# esp32c2_devboard.net
KiCad netlist of a schematic drawn in Altium Designer
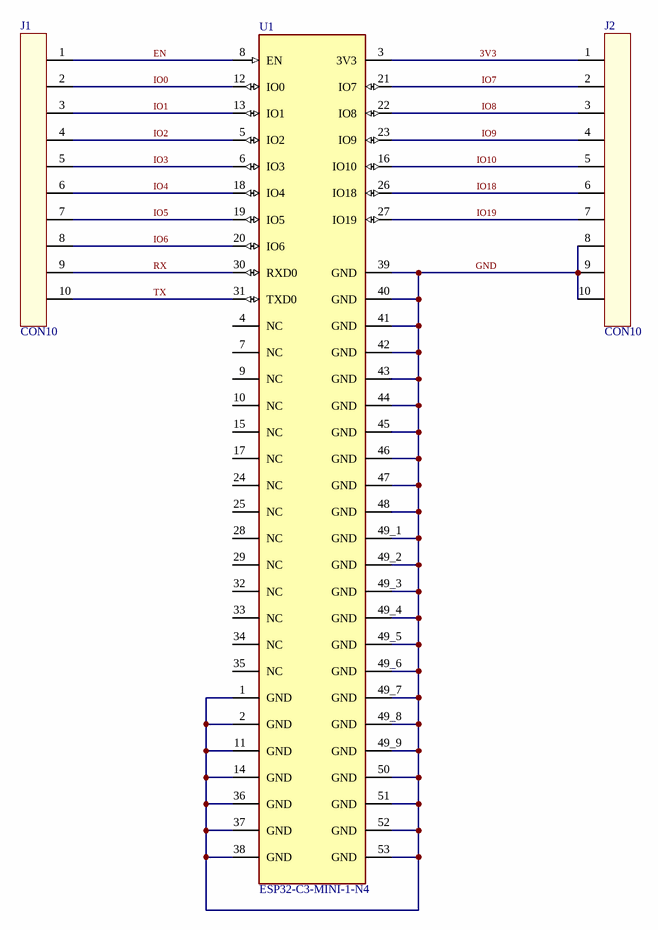
[diagram p0: esp32c2_devboard.SchDoc]

(export (version "E")
  (design (tool "Eeschema 10.0.6"))
  (components
    (comp (ref "J1") (value "CON10") (footprint "CON10") (libsource (lib "") (part "CON10_1")))
    (comp (ref "J2") (value "CON10") (footprint "CON10") (libsource (lib "esp32c2_devboard") (part "CON10")))
    (comp (ref "U1")
      (value "ESP32-C3-MINI-1-N4")
      (footprint "XCVR_ESP32-C3-MINI-1-N4")
      (fields (field (name "MF") "Espressif Systems"))
      (libsource (lib "esp32c2_devboard") (part "ESP32-C3-MINI-1-N4"))
    )
  )
  (nets
    (net (code "1") (name "/3V3") (class "Default")
      (node (ref "J2") (pin "1") (pintype "passive"))
      (node (ref "U1") (pin "3") (pinfunction "3V3_3") (pintype "power_in"))
    )
    (net (code "2") (name "/EN") (class "Default")
      (node (ref "J1") (pin "1") (pintype "passive"))
      (node (ref "U1") (pin "8") (pinfunction "EN_8") (pintype "input"))
    )
    (net (code "3") (name "/GND") (class "Default")
      (node (ref "J2") (pin "10") (pintype "passive"))
      (node (ref "J2") (pin "8") (pintype "passive"))
      (node (ref "J2") (pin "9") (pintype "passive"))
      (node (ref "U1") (pin "1") (pinfunction "GND_1") (pintype "power_in"))
      (node (ref "U1") (pin "11") (pinfunction "GND_11") (pintype "power_in"))
      (node (ref "U1") (pin "14") (pinfunction "GND_14") (pintype "power_in"))
      (node (ref "U1") (pin "2") (pinfunction "GND_2") (pintype "power_in"))
      (node (ref "U1") (pin "36") (pinfunction "GND_36") (pintype "power_in"))
      (node (ref "U1") (pin "37") (pinfunction "GND_37") (pintype "power_in"))
      (node (ref "U1") (pin "38") (pinfunction "GND_38") (pintype "power_in"))
      (node (ref "U1") (pin "39") (pinfunction "GND_39") (pintype "power_in"))
      (node (ref "U1") (pin "40") (pinfunction "GND_40") (pintype "power_in"))
      (node (ref "U1") (pin "41") (pinfunction "GND_41") (pintype "power_in"))
      (node (ref "U1") (pin "42") (pinfunction "GND_42") (pintype "power_in"))
      (node (ref "U1") (pin "43") (pinfunction "GND_43") (pintype "power_in"))
      (node (ref "U1") (pin "44") (pinfunction "GND_44") (pintype "power_in"))
      (node (ref "U1") (pin "45") (pinfunction "GND_45") (pintype "power_in"))
      (node (ref "U1") (pin "46") (pinfunction "GND_46") (pintype "power_in"))
      (node (ref "U1") (pin "47") (pinfunction "GND_47") (pintype "power_in"))
      (node (ref "U1") (pin "48") (pinfunction "GND_48") (pintype "power_in"))
      (node (ref "U1") (pin "49_1") (pinfunction "GND_49_1") (pintype "power_in"))
      (node (ref "U1") (pin "49_2") (pinfunction "GND_49_2") (pintype "power_in"))
      (node (ref "U1") (pin "49_3") (pinfunction "GND_49_3") (pintype "power_in"))
      (node (ref "U1") (pin "49_4") (pinfunction "GND_49_4") (pintype "power_in"))
      (node (ref "U1") (pin "49_5") (pinfunction "GND_49_5") (pintype "power_in"))
      (node (ref "U1") (pin "49_6") (pinfunction "GND_49_6") (pintype "power_in"))
      (node (ref "U1") (pin "49_7") (pinfunction "GND_49_7") (pintype "power_in"))
      (node (ref "U1") (pin "49_8") (pinfunction "GND_49_8") (pintype "power_in"))
      (node (ref "U1") (pin "49_9") (pinfunction "GND_49_9") (pintype "power_in"))
      (node (ref "U1") (pin "50") (pinfunction "GND_50") (pintype "power_in"))
      (node (ref "U1") (pin "51") (pinfunction "GND_51") (pintype "power_in"))
      (node (ref "U1") (pin "52") (pinfunction "GND_52") (pintype "power_in"))
      (node (ref "U1") (pin "53") (pinfunction "GND_53") (pintype "power_in"))
    )
    (net (code "4") (name "/IO0") (class "Default")
      (node (ref "J1") (pin "2") (pintype "passive"))
      (node (ref "U1") (pin "12") (pinfunction "IO0_12") (pintype "bidirectional"))
    )
    (net (code "5") (name "/IO1") (class "Default")
      (node (ref "J1") (pin "3") (pintype "passive"))
      (node (ref "U1") (pin "13") (pinfunction "IO1_13") (pintype "bidirectional"))
    )
    (net (code "6") (name "/IO2") (class "Default")
      (node (ref "J1") (pin "4") (pintype "passive"))
      (node (ref "U1") (pin "5") (pinfunction "IO2_5") (pintype "bidirectional"))
    )
    (net (code "7") (name "/IO3") (class "Default")
      (node (ref "J1") (pin "5") (pintype "passive"))
      (node (ref "U1") (pin "6") (pinfunction "IO3_6") (pintype "bidirectional"))
    )
    (net (code "8") (name "/IO4") (class "Default")
      (node (ref "J1") (pin "6") (pintype "passive"))
      (node (ref "U1") (pin "18") (pinfunction "IO4_18") (pintype "bidirectional"))
    )
    (net (code "9") (name "/IO5") (class "Default")
      (node (ref "J1") (pin "7") (pintype "passive"))
      (node (ref "U1") (pin "19") (pinfunction "IO5_19") (pintype "bidirectional"))
    )
    (net (code "10") (name "/IO6") (class "Default")
      (node (ref "J1") (pin "8") (pintype "passive"))
      (node (ref "U1") (pin "20") (pinfunction "IO6_20") (pintype "bidirectional"))
    )
    (net (code "11") (name "/IO7") (class "Default")
      (node (ref "J2") (pin "2") (pintype "passive"))
      (node (ref "U1") (pin "21") (pinfunction "IO7_21") (pintype "bidirectional"))
    )
    (net (code "12") (name "/IO8") (class "Default")
      (node (ref "J2") (pin "3") (pintype "passive"))
      (node (ref "U1") (pin "22") (pinfunction "IO8_22") (pintype "bidirectional"))
    )
    (net (code "13") (name "/IO9") (class "Default")
      (node (ref "J2") (pin "4") (pintype "passive"))
      (node (ref "U1") (pin "23") (pinfunction "IO9_23") (pintype "bidirectional"))
    )
    (net (code "14") (name "/IO10") (class "Default")
      (node (ref "J2") (pin "5") (pintype "passive"))
      (node (ref "U1") (pin "16") (pinfunction "IO10_16") (pintype "bidirectional"))
    )
    (net (code "15") (name "/IO18") (class "Default")
      (node (ref "J2") (pin "6") (pintype "passive"))
      (node (ref "U1") (pin "26") (pinfunction "IO18_26") (pintype "bidirectional"))
    )
    (net (code "16") (name "/IO19") (class "Default")
      (node (ref "J2") (pin "7") (pintype "passive"))
      (node (ref "U1") (pin "27") (pinfunction "IO19_27") (pintype "bidirectional"))
    )
    (net (code "17") (name "/RX") (class "Default")
      (node (ref "J1") (pin "9") (pintype "passive"))
      (node (ref "U1") (pin "30") (pinfunction "RXD0_30") (pintype "bidirectional"))
    )
    (net (code "18") (name "/TX") (class "Default")
      (node (ref "J1") (pin "10") (pintype "passive"))
      (node (ref "U1") (pin "31") (pinfunction "TXD0_31") (pintype "bidirectional"))
    )
    (net (code "19") (name "unconnected-(U1-NC-Pad4)") (class "Default")
      (node (ref "U1") (pin "4") (pinfunction "NC_4") (pintype "passive"))
    )
    (net (code "20") (name "unconnected-(U1-NC-Pad7)") (class "Default")
      (node (ref "U1") (pin "7") (pinfunction "NC_7") (pintype "passive"))
    )
    (net (code "21") (name "unconnected-(U1-NC-Pad9)") (class "Default")
      (node (ref "U1") (pin "9") (pinfunction "NC_9") (pintype "passive"))
    )
    (net (code "22") (name "unconnected-(U1-NC-Pad10)") (class "Default")
      (node (ref "U1") (pin "10") (pinfunction "NC_10") (pintype "passive"))
    )
    (net (code "23") (name "unconnected-(U1-NC-Pad15)") (class "Default")
      (node (ref "U1") (pin "15") (pinfunction "NC_15") (pintype "passive"))
    )
    (net (code "24") (name "unconnected-(U1-NC-Pad17)") (class "Default")
      (node (ref "U1") (pin "17") (pinfunction "NC_17") (pintype "passive"))
    )
    (net (code "25") (name "unconnected-(U1-NC-Pad24)") (class "Default")
      (node (ref "U1") (pin "24") (pinfunction "NC_24") (pintype "passive"))
    )
    (net (code "26") (name "unconnected-(U1-NC-Pad25)") (class "Default")
      (node (ref "U1") (pin "25") (pinfunction "NC_25") (pintype "passive"))
    )
    (net (code "27") (name "unconnected-(U1-NC-Pad28)") (class "Default")
      (node (ref "U1") (pin "28") (pinfunction "NC_28") (pintype "passive"))
    )
    (net (code "28") (name "unconnected-(U1-NC-Pad29)") (class "Default")
      (node (ref "U1") (pin "29") (pinfunction "NC_29") (pintype "passive"))
    )
    (net (code "29") (name "unconnected-(U1-NC-Pad32)") (class "Default")
      (node (ref "U1") (pin "32") (pinfunction "NC_32") (pintype "passive"))
    )
    (net (code "30") (name "unconnected-(U1-NC-Pad33)") (class "Default")
      (node (ref "U1") (pin "33") (pinfunction "NC_33") (pintype "passive"))
    )
    (net (code "31") (name "unconnected-(U1-NC-Pad34)") (class "Default")
      (node (ref "U1") (pin "34") (pinfunction "NC_34") (pintype "passive"))
    )
    (net (code "32") (name "unconnected-(U1-NC-Pad35)") (class "Default")
      (node (ref "U1") (pin "35") (pinfunction "NC_35") (pintype "passive"))
    )
  )
)
